# misc.net
KiCad netlist of a schematic drawn in Altium Designer
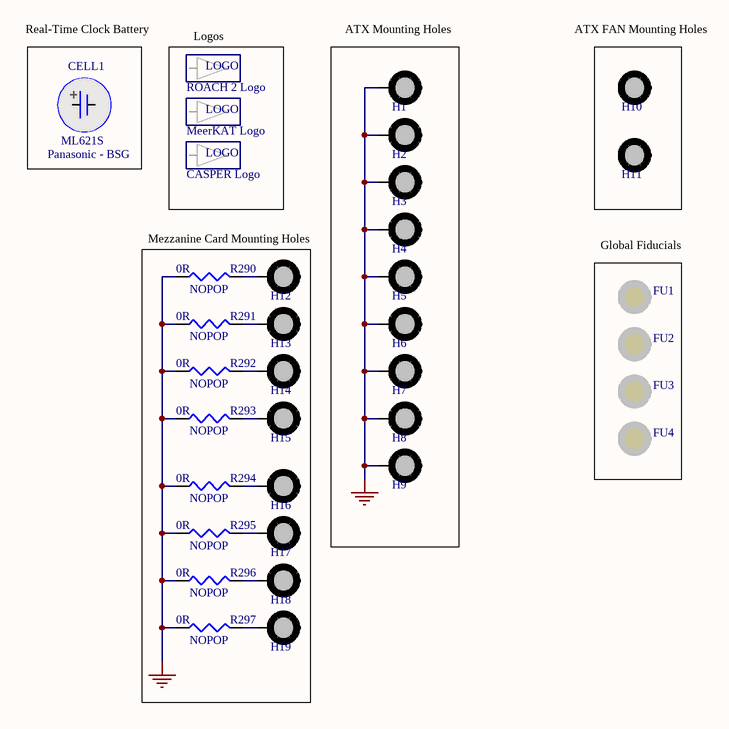
[diagram p0: misc.SchDoc]

(export (version "E")
  (design (tool "Eeschema 10.0.6"))
  (components
    (comp (ref "CELL1")
      (value "ML621S")
      (description "3V,  6.8mm Mangenese Lithium Battery")
      (fields (field (name "PARTNUM") "ML621S") (field (name "MANUFACTURER") "Panasonic - BSG"))
      (libsource (lib "altium_db") (part "ML621S"))
    )
    (comp (ref "FU1")
      (value "FIDUCIAL")
      (footprint "FIDUCIAL_1MM")
      (description "1mm Fiducial mark")
      (libsource (lib "altium_db") (part "FIDUCIAL"))
    )
    (comp (ref "FU2")
      (value "FIDUCIAL")
      (footprint "FIDUCIAL_1MM")
      (description "1mm Fiducial mark")
      (libsource (lib "altium_db") (part "FIDUCIAL"))
    )
    (comp (ref "FU3")
      (value "FIDUCIAL")
      (footprint "FIDUCIAL_1MM")
      (description "1mm Fiducial mark")
      (libsource (lib "altium_db") (part "FIDUCIAL"))
    )
    (comp (ref "FU4")
      (value "FIDUCIAL")
      (footprint "FIDUCIAL_1MM")
      (description "1mm Fiducial mark")
      (libsource (lib "altium_db") (part "FIDUCIAL"))
    )
    (comp (ref "H1")
      (value "MH_ATX")
      (footprint "MH_ATX")
      (description "3.81mm Diameter, ATX mounting hole")
      (libsource (lib "altium_db") (part "MH_ATX"))
    )
    (comp (ref "H2")
      (value "MH_ATX")
      (footprint "MH_ATX")
      (description "3.81mm Diameter, ATX mounting hole")
      (libsource (lib "altium_db") (part "MH_ATX"))
    )
    (comp (ref "H3")
      (value "MH_ATX")
      (footprint "MH_ATX")
      (description "3.81mm Diameter, ATX mounting hole")
      (libsource (lib "altium_db") (part "MH_ATX"))
    )
    (comp (ref "H4")
      (value "MH_ATX")
      (footprint "MH_ATX")
      (description "3.81mm Diameter, ATX mounting hole")
      (libsource (lib "altium_db") (part "MH_ATX"))
    )
    (comp (ref "H5")
      (value "MH_ATX")
      (footprint "MH_ATX")
      (description "3.81mm Diameter, ATX mounting hole")
      (libsource (lib "altium_db") (part "MH_ATX"))
    )
    (comp (ref "H6")
      (value "MH_ATX")
      (footprint "MH_ATX")
      (description "3.81mm Diameter, ATX mounting hole")
      (libsource (lib "altium_db") (part "MH_ATX"))
    )
    (comp (ref "H7")
      (value "MH_ATX")
      (footprint "MH_ATX")
      (description "3.81mm Diameter, ATX mounting hole")
      (libsource (lib "altium_db") (part "MH_ATX"))
    )
    (comp (ref "H8")
      (value "MH_ATX")
      (footprint "MH_ATX")
      (description "3.81mm Diameter, ATX mounting hole")
      (libsource (lib "altium_db") (part "MH_ATX"))
    )
    (comp (ref "H9")
      (value "MH_ATX")
      (footprint "MH_ATX")
      (description "3.81mm Diameter, ATX mounting hole")
      (libsource (lib "altium_db") (part "MH_ATX"))
    )
    (comp (ref "H10")
      (value "MH_NC")
      (footprint "MH_FANATX")
      (description "3.2mm Diameter, Unplated, Floating mounting Hole")
      (libsource (lib "altium_db") (part "MH_NC"))
    )
    (comp (ref "H11")
      (value "MH_NC")
      (footprint "MH_FANATX")
      (description "3.2mm Diameter, Unplated, Floating mounting Hole")
      (libsource (lib "altium_db") (part "MH_NC"))
    )
    (comp (ref "H12")
      (value "MH_ATX")
      (footprint "MH_ATX")
      (description "3.81mm Diameter, ATX mounting hole")
      (libsource (lib "altium_db") (part "MH_ATX"))
    )
    (comp (ref "H13")
      (value "MH_ATX")
      (footprint "MH_ATX")
      (description "3.81mm Diameter, ATX mounting hole")
      (libsource (lib "altium_db") (part "MH_ATX"))
    )
    (comp (ref "H14")
      (value "MH_ATX")
      (footprint "MH_ATX")
      (description "3.81mm Diameter, ATX mounting hole")
      (libsource (lib "altium_db") (part "MH_ATX"))
    )
    (comp (ref "H15")
      (value "MH_ATX")
      (footprint "MH_ATX")
      (description "3.81mm Diameter, ATX mounting hole")
      (libsource (lib "altium_db") (part "MH_ATX"))
    )
    (comp (ref "H16")
      (value "MH_ATX")
      (footprint "MH_ATX")
      (description "3.81mm Diameter, ATX mounting hole")
      (libsource (lib "altium_db") (part "MH_ATX"))
    )
    (comp (ref "H17")
      (value "MH_ATX")
      (footprint "MH_ATX")
      (description "3.81mm Diameter, ATX mounting hole")
      (libsource (lib "altium_db") (part "MH_ATX"))
    )
    (comp (ref "H18")
      (value "MH_ATX")
      (footprint "MH_ATX")
      (description "3.81mm Diameter, ATX mounting hole")
      (libsource (lib "altium_db") (part "MH_ATX"))
    )
    (comp (ref "H19")
      (value "MH_ATX")
      (footprint "MH_ATX")
      (description "3.81mm Diameter, ATX mounting hole")
      (libsource (lib "altium_db") (part "MH_ATX"))
    )
    (comp (ref "LOGO1")
      (value "ROACH 2 Logo")
      (footprint "ROACH2_LOGO")
      (libsource (lib "altium_db") (part "LOGO"))
    )
    (comp (ref "LOGO2")
      (value "MeerKAT Logo")
      (footprint "MEERKAT_LOGO")
      (libsource (lib "altium_db") (part "LOGO"))
    )
    (comp (ref "LOGO3")
      (value "CASPER Logo")
      (footprint "CASPER_LOGO")
      (libsource (lib "altium_db") (part "LOGO"))
    )
    (comp (ref "R290")
      (value "0R")
      (footprint "RESC1005X40L")
      (description "0R, 1.1mm x 0.5mm, Thick Film Resistor")
      (fields (field (name "MANUFACTURER") "ROYALOHM") (field (name "PARTNUM") "0402WG00000T1E"))
      (libsource (lib "altium_db") (part "ResStd"))
    )
    (comp (ref "R291")
      (value "0R")
      (footprint "RESC1005X40L")
      (description "0R, 1.1mm x 0.5mm, Thick Film Resistor")
      (fields (field (name "MANUFACTURER") "ROYALOHM") (field (name "PARTNUM") "0402WG00000T1E"))
      (libsource (lib "altium_db") (part "ResStd"))
    )
    (comp (ref "R292")
      (value "0R")
      (footprint "RESC1005X40L")
      (description "0R, 1.1mm x 0.5mm, Thick Film Resistor")
      (fields (field (name "MANUFACTURER") "ROYALOHM") (field (name "PARTNUM") "0402WG00000T1E"))
      (libsource (lib "altium_db") (part "ResStd"))
    )
    (comp (ref "R293")
      (value "0R")
      (footprint "RESC1005X40L")
      (description "0R, 1.1mm x 0.5mm, Thick Film Resistor")
      (fields (field (name "MANUFACTURER") "ROYALOHM") (field (name "PARTNUM") "0402WG00000T1E"))
      (libsource (lib "altium_db") (part "ResStd"))
    )
    (comp (ref "R294")
      (value "0R")
      (footprint "RESC1005X40L")
      (description "0R, 1.1mm x 0.5mm, Thick Film Resistor")
      (fields (field (name "MANUFACTURER") "ROYALOHM") (field (name "PARTNUM") "0402WG00000T1E"))
      (libsource (lib "altium_db") (part "ResStd"))
    )
    (comp (ref "R295")
      (value "0R")
      (footprint "RESC1005X40L")
      (description "0R, 1.1mm x 0.5mm, Thick Film Resistor")
      (fields (field (name "MANUFACTURER") "ROYALOHM") (field (name "PARTNUM") "0402WG00000T1E"))
      (libsource (lib "altium_db") (part "ResStd"))
    )
    (comp (ref "R296")
      (value "0R")
      (footprint "RESC1005X40L")
      (description "0R, 1.1mm x 0.5mm, Thick Film Resistor")
      (fields (field (name "MANUFACTURER") "ROYALOHM") (field (name "PARTNUM") "0402WG00000T1E"))
      (libsource (lib "altium_db") (part "ResStd"))
    )
    (comp (ref "R297")
      (value "0R")
      (footprint "RESC1005X40L")
      (description "0R, 1.1mm x 0.5mm, Thick Film Resistor")
      (fields (field (name "MANUFACTURER") "ROYALOHM") (field (name "PARTNUM") "0402WG00000T1E"))
      (libsource (lib "altium_db") (part "ResStd"))
    )
  )
  (nets
    (net (code "1") (name "GND") (class "Default")
      (node (ref "H1") (pin "1") (pinfunction "0_1") (pintype "passive"))
      (node (ref "H2") (pin "1") (pinfunction "0_1") (pintype "passive"))
      (node (ref "H3") (pin "1") (pinfunction "0_1") (pintype "passive"))
      (node (ref "H4") (pin "1") (pinfunction "0_1") (pintype "passive"))
      (node (ref "H5") (pin "1") (pinfunction "0_1") (pintype "passive"))
      (node (ref "H6") (pin "1") (pinfunction "0_1") (pintype "passive"))
      (node (ref "H7") (pin "1") (pinfunction "0_1") (pintype "passive"))
      (node (ref "H8") (pin "1") (pinfunction "0_1") (pintype "passive"))
      (node (ref "H9") (pin "1") (pinfunction "0_1") (pintype "passive"))
      (node (ref "R290") (pin "1") (pinfunction "1_1") (pintype "passive"))
      (node (ref "R291") (pin "1") (pinfunction "1_1") (pintype "passive"))
      (node (ref "R292") (pin "1") (pinfunction "1_1") (pintype "passive"))
      (node (ref "R293") (pin "1") (pinfunction "1_1") (pintype "passive"))
      (node (ref "R294") (pin "1") (pinfunction "1_1") (pintype "passive"))
      (node (ref "R295") (pin "1") (pinfunction "1_1") (pintype "passive"))
      (node (ref "R296") (pin "1") (pinfunction "1_1") (pintype "passive"))
      (node (ref "R297") (pin "1") (pinfunction "1_1") (pintype "passive"))
    )
    (net (code "2") (name "Net-(H12-0)") (class "Default")
      (node (ref "H12") (pin "1") (pinfunction "0_1") (pintype "passive"))
      (node (ref "R290") (pin "2") (pinfunction "2_2") (pintype "passive"))
    )
    (net (code "3") (name "Net-(H13-0)") (class "Default")
      (node (ref "H13") (pin "1") (pinfunction "0_1") (pintype "passive"))
      (node (ref "R291") (pin "2") (pinfunction "2_2") (pintype "passive"))
    )
    (net (code "4") (name "Net-(H14-0)") (class "Default")
      (node (ref "H14") (pin "1") (pinfunction "0_1") (pintype "passive"))
      (node (ref "R292") (pin "2") (pinfunction "2_2") (pintype "passive"))
    )
    (net (code "5") (name "Net-(H15-0)") (class "Default")
      (node (ref "H15") (pin "1") (pinfunction "0_1") (pintype "passive"))
      (node (ref "R293") (pin "2") (pinfunction "2_2") (pintype "passive"))
    )
    (net (code "6") (name "Net-(H16-0)") (class "Default")
      (node (ref "H16") (pin "1") (pinfunction "0_1") (pintype "passive"))
      (node (ref "R294") (pin "2") (pinfunction "2_2") (pintype "passive"))
    )
    (net (code "7") (name "Net-(H17-0)") (class "Default")
      (node (ref "H17") (pin "1") (pinfunction "0_1") (pintype "passive"))
      (node (ref "R295") (pin "2") (pinfunction "2_2") (pintype "passive"))
    )
    (net (code "8") (name "Net-(H18-0)") (class "Default")
      (node (ref "H18") (pin "1") (pinfunction "0_1") (pintype "passive"))
      (node (ref "R296") (pin "2") (pinfunction "2_2") (pintype "passive"))
    )
    (net (code "9") (name "Net-(H19-0)") (class "Default")
      (node (ref "H19") (pin "1") (pinfunction "0_1") (pintype "passive"))
      (node (ref "R297") (pin "2") (pinfunction "2_2") (pintype "passive"))
    )
  )
)
